# NRF52.net
KiCad netlist of a schematic drawn in Altium Designer
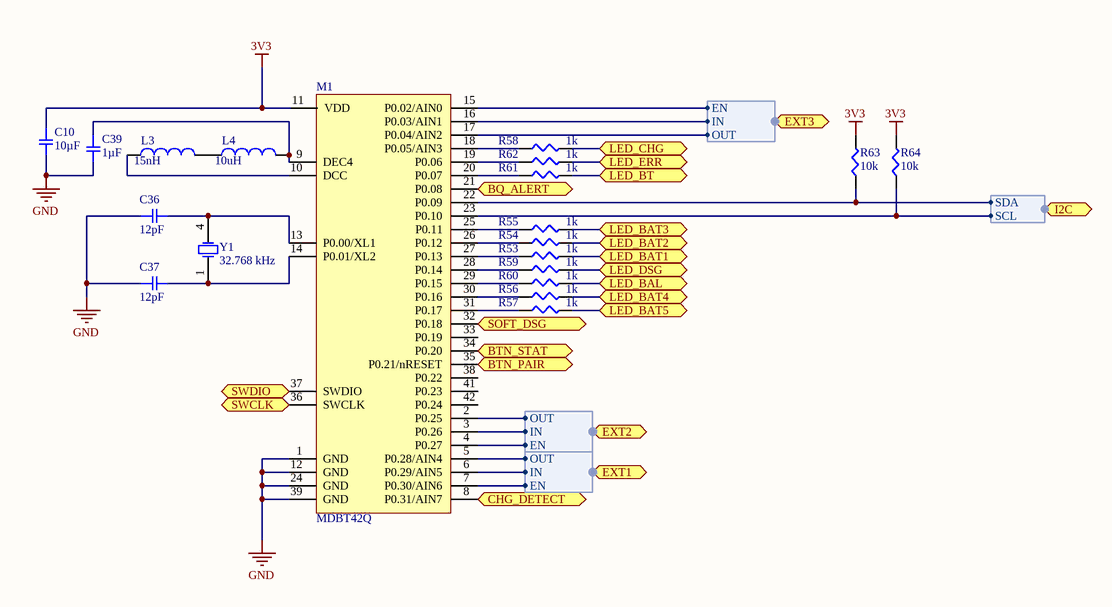
[diagram p0: NRF52.SchDoc]

(export (version "E")
  (design (tool "Eeschema 10.0.6"))
  (components
    (comp (ref "C10")
      (value "10µF")
      (footprint "SMD-0603C")
      (description "CAP CER 10UF 6.3V X5R 0603")
      (fields
        (field (name "DIGI-KEY PART NUMBER") "490-10467-1-ND")
        (field (name "PART NUMBER") "GRM185R60J106ME15D")
      )
      (libsource (lib "capacitor_murata_0603") (part "GRM185R60J106ME15D"))
    )
    (comp (ref "C36")
      (value "12pF")
      (footprint "SMD-0603C")
      (description "CAP CER 12PF 50V NP0 0603")
      (fields
        (field (name "DIGI-KEY PART NUMBER") "490-6045-1-ND")
        (field (name "PART NUMBER") "GCM1885C1H120JA16D")
      )
      (libsource (lib "capacitor_murata_0603") (part "GCM1885C1H120JA16D"))
    )
    (comp (ref "C37")
      (value "12pF")
      (footprint "SMD-0603C")
      (description "CAP CER 12PF 50V NP0 0603")
      (fields
        (field (name "DIGI-KEY PART NUMBER") "490-6045-1-ND")
        (field (name "PART NUMBER") "GCM1885C1H120JA16D")
      )
      (libsource (lib "capacitor_murata_0603") (part "GCM1885C1H120JA16D"))
    )
    (comp (ref "C39")
      (value "1µF")
      (footprint "SMD-0603C")
      (description "CAP CER 1UF 16V X7R 0603")
      (fields
        (field (name "DIGI-KEY PART NUMBER") "490-5241-1-ND")
        (field (name "PART NUMBER") "GCM188R71C105KA64D")
      )
      (libsource (lib "capacitor_murata_0603") (part "GCM188R71C105KA64D"))
    )
    (comp (ref "L3")
      (value "15nH")
      (footprint "0402-A")
      (description "Inductor")
      (fields (field (name "PUBLISHER") "Altium Limited"))
      (libsource (lib "Miscellaneous Devices") (part "Inductor"))
    )
    (comp (ref "L4")
      (value "10uH")
      (footprint "0402-A")
      (description "Inductor")
      (fields (field (name "PUBLISHER") "Altium Limited"))
      (libsource (lib "Miscellaneous Devices") (part "Inductor"))
    )
    (comp (ref "M1")
      (value "MDBT42Q")
      (footprint "MDBT42Q")
      (description "nRF52832 module")
      (libsource (lib "Components") (part "MDBT42Q"))
    )
    (comp (ref "R53")
      (value "1k")
      (footprint "SMD-0603-RES")
      (description "RES SMD 1K OHM 1% 1/10W 0603")
      (fields
        (field (name "PART NUMBER") "ERJ-3EKF1001V")
        (field (name "DIGI-KEY PART NUMBER") "P1.00KHCT-ND")
      )
      (libsource (lib "Panasonic_ERJ_0603") (part "ERJ-3EKF1001V"))
    )
    (comp (ref "R54")
      (value "1k")
      (footprint "SMD-0603-RES")
      (description "RES SMD 1K OHM 1% 1/10W 0603")
      (fields
        (field (name "PART NUMBER") "ERJ-3EKF1001V")
        (field (name "DIGI-KEY PART NUMBER") "P1.00KHCT-ND")
      )
      (libsource (lib "Panasonic_ERJ_0603") (part "ERJ-3EKF1001V"))
    )
    (comp (ref "R55")
      (value "1k")
      (footprint "SMD-0603-RES")
      (description "RES SMD 1K OHM 1% 1/10W 0603")
      (fields
        (field (name "PART NUMBER") "ERJ-3EKF1001V")
        (field (name "DIGI-KEY PART NUMBER") "P1.00KHCT-ND")
      )
      (libsource (lib "Panasonic_ERJ_0603") (part "ERJ-3EKF1001V"))
    )
    (comp (ref "R56")
      (value "1k")
      (footprint "SMD-0603-RES")
      (description "RES SMD 1K OHM 1% 1/10W 0603")
      (fields
        (field (name "PART NUMBER") "ERJ-3EKF1001V")
        (field (name "DIGI-KEY PART NUMBER") "P1.00KHCT-ND")
      )
      (libsource (lib "Panasonic_ERJ_0603") (part "ERJ-3EKF1001V"))
    )
    (comp (ref "R57")
      (value "1k")
      (footprint "SMD-0603-RES")
      (description "RES SMD 1K OHM 1% 1/10W 0603")
      (fields
        (field (name "PART NUMBER") "ERJ-3EKF1001V")
        (field (name "DIGI-KEY PART NUMBER") "P1.00KHCT-ND")
      )
      (libsource (lib "Panasonic_ERJ_0603") (part "ERJ-3EKF1001V"))
    )
    (comp (ref "R58")
      (value "1k")
      (footprint "SMD-0603-RES")
      (description "RES SMD 1K OHM 1% 1/10W 0603")
      (fields
        (field (name "PART NUMBER") "ERJ-3EKF1001V")
        (field (name "DIGI-KEY PART NUMBER") "P1.00KHCT-ND")
      )
      (libsource (lib "Panasonic_ERJ_0603") (part "ERJ-3EKF1001V"))
    )
    (comp (ref "R59")
      (value "1k")
      (footprint "SMD-0603-RES")
      (description "RES SMD 1K OHM 1% 1/10W 0603")
      (fields
        (field (name "PART NUMBER") "ERJ-3EKF1001V")
        (field (name "DIGI-KEY PART NUMBER") "P1.00KHCT-ND")
      )
      (libsource (lib "Panasonic_ERJ_0603") (part "ERJ-3EKF1001V"))
    )
    (comp (ref "R60")
      (value "1k")
      (footprint "SMD-0603-RES")
      (description "RES SMD 1K OHM 1% 1/10W 0603")
      (fields
        (field (name "PART NUMBER") "ERJ-3EKF1001V")
        (field (name "DIGI-KEY PART NUMBER") "P1.00KHCT-ND")
      )
      (libsource (lib "Panasonic_ERJ_0603") (part "ERJ-3EKF1001V"))
    )
    (comp (ref "R61")
      (value "1k")
      (footprint "SMD-0603-RES")
      (description "RES SMD 1K OHM 1% 1/10W 0603")
      (fields
        (field (name "PART NUMBER") "ERJ-3EKF1001V")
        (field (name "DIGI-KEY PART NUMBER") "P1.00KHCT-ND")
      )
      (libsource (lib "Panasonic_ERJ_0603") (part "ERJ-3EKF1001V"))
    )
    (comp (ref "R62")
      (value "1k")
      (footprint "SMD-0603-RES")
      (description "RES SMD 1K OHM 1% 1/10W 0603")
      (fields
        (field (name "PART NUMBER") "ERJ-3EKF1001V")
        (field (name "DIGI-KEY PART NUMBER") "P1.00KHCT-ND")
      )
      (libsource (lib "Panasonic_ERJ_0603") (part "ERJ-3EKF1001V"))
    )
    (comp (ref "R63")
      (value "10k")
      (footprint "SMD-0603-RES")
      (description "RES SMD 10K OHM 1% 1/10W 0603")
      (fields
        (field (name "PART NUMBER") "ERJ-3EKF1002V")
        (field (name "DIGI-KEY PART NUMBER") "P10.0KHCT-ND")
      )
      (libsource (lib "Panasonic_ERJ_0603") (part "ERJ-3EKF1002V"))
    )
    (comp (ref "R64")
      (value "10k")
      (footprint "SMD-0603-RES")
      (description "RES SMD 10K OHM 1% 1/10W 0603")
      (fields
        (field (name "PART NUMBER") "ERJ-3EKF1002V")
        (field (name "DIGI-KEY PART NUMBER") "P10.0KHCT-ND")
      )
      (libsource (lib "Panasonic_ERJ_0603") (part "ERJ-3EKF1002V"))
    )
    (comp (ref "Y1")
      (value "32.768 kHz")
      (footprint "LFXTAL")
      (description "LFXTAL016178")
      (fields (field (name "PUBLISHER") "Altium Limited"))
      (libsource (lib "Components") (part "LFXTAL016178"))
    )
  )
  (nets
    (net (code "3") (name "/BQ_ALERT") (class "Default")
      (node (ref "M1") (pin "21") (pinfunction "P0.08_21") (pintype "passive"))
    )
    (net (code "4") (name "/BTN_PAIR") (class "Default")
      (node (ref "M1") (pin "35") (pinfunction "P0.21/nRESET_35") (pintype "passive"))
    )
    (net (code "5") (name "/BTN_STAT") (class "Default")
      (node (ref "M1") (pin "34") (pinfunction "P0.20_34") (pintype "passive"))
    )
    (net (code "6") (name "/CHG_DETECT") (class "Default")
      (node (ref "M1") (pin "8") (pinfunction "P0.31/AIN7_8") (pintype "passive"))
    )
    (net (code "7") (name "/LED_BAL") (class "Default")
      (node (ref "R60") (pin "2") (pinfunction "2_2") (pintype "passive"))
    )
    (net (code "8") (name "/LED_BAT1") (class "Default")
      (node (ref "R53") (pin "2") (pinfunction "2_2") (pintype "passive"))
    )
    (net (code "9") (name "/LED_BAT2") (class "Default")
      (node (ref "R54") (pin "2") (pinfunction "2_2") (pintype "passive"))
    )
    (net (code "10") (name "/LED_BAT3") (class "Default")
      (node (ref "R55") (pin "2") (pinfunction "2_2") (pintype "passive"))
    )
    (net (code "11") (name "/LED_BAT4") (class "Default")
      (node (ref "R56") (pin "2") (pinfunction "2_2") (pintype "passive"))
    )
    (net (code "12") (name "/LED_BAT5") (class "Default")
      (node (ref "R57") (pin "2") (pinfunction "2_2") (pintype "passive"))
    )
    (net (code "13") (name "/LED_BT") (class "Default")
      (node (ref "R61") (pin "2") (pinfunction "2_2") (pintype "passive"))
    )
    (net (code "14") (name "/LED_CHG") (class "Default")
      (node (ref "R58") (pin "2") (pinfunction "2_2") (pintype "passive"))
    )
    (net (code "15") (name "/LED_DSG") (class "Default")
      (node (ref "R59") (pin "2") (pinfunction "2_2") (pintype "passive"))
    )
    (net (code "16") (name "/LED_ERR") (class "Default")
      (node (ref "R62") (pin "2") (pinfunction "2_2") (pintype "passive"))
    )
    (net (code "17") (name "/SCL") (class "Default")
      (node (ref "M1") (pin "23") (pinfunction "P0.10_23") (pintype "passive"))
      (node (ref "R64") (pin "1") (pinfunction "1_1") (pintype "passive"))
    )
    (net (code "18") (name "/SDA") (class "Default")
      (node (ref "M1") (pin "22") (pinfunction "P0.09_22") (pintype "passive"))
      (node (ref "R63") (pin "1") (pinfunction "1_1") (pintype "passive"))
    )
    (net (code "19") (name "/SOFT_DSG") (class "Default")
      (node (ref "M1") (pin "32") (pinfunction "P0.18_32") (pintype "passive"))
    )
    (net (code "20") (name "/SWCLK") (class "Default")
      (node (ref "M1") (pin "36") (pinfunction "SWCLK_36") (pintype "passive"))
    )
    (net (code "21") (name "/SWDIO") (class "Default")
      (node (ref "M1") (pin "37") (pinfunction "SWDIO_37") (pintype "passive"))
    )
    (net (code "24") (name "3V3") (class "Default")
      (node (ref "C10") (pin "1") (pinfunction "1_1") (pintype "passive"))
      (node (ref "M1") (pin "11") (pinfunction "VDD_11") (pintype "passive"))
      (node (ref "R63") (pin "2") (pinfunction "2_2") (pintype "passive"))
      (node (ref "R64") (pin "2") (pinfunction "2_2") (pintype "passive"))
    )
    (net (code "25") (name "GND") (class "Default")
      (node (ref "C10") (pin "2") (pinfunction "2_2") (pintype "passive"))
      (node (ref "C36") (pin "1") (pinfunction "1_1") (pintype "passive"))
      (node (ref "C37") (pin "1") (pinfunction "1_1") (pintype "passive"))
      (node (ref "C39") (pin "2") (pinfunction "2_2") (pintype "passive"))
      (node (ref "M1") (pin "1") (pinfunction "GND_1") (pintype "passive"))
      (node (ref "M1") (pin "12") (pinfunction "GND_12") (pintype "passive"))
      (node (ref "M1") (pin "24") (pinfunction "GND_24") (pintype "passive"))
      (node (ref "M1") (pin "39") (pinfunction "GND_39") (pintype "passive"))
    )
    (net (code "26") (name "Net-(L3-Pad2)") (class "Default")
      (node (ref "L3") (pin "2") (pinfunction "2_2") (pintype "passive"))
      (node (ref "L4") (pin "1") (pinfunction "1_1") (pintype "passive"))
    )
    (net (code "27") (name "Net-(M1-DCC)") (class "Default")
      (node (ref "L3") (pin "1") (pinfunction "1_1") (pintype "passive"))
      (node (ref "M1") (pin "10") (pinfunction "DCC_10") (pintype "passive"))
    )
    (net (code "28") (name "Net-(M1-DEC4)") (class "Default")
      (node (ref "C39") (pin "1") (pinfunction "1_1") (pintype "passive"))
      (node (ref "L4") (pin "2") (pinfunction "2_2") (pintype "passive"))
      (node (ref "M1") (pin "9") (pinfunction "DEC4_9") (pintype "passive"))
    )
    (net (code "29") (name "Net-(M1-P0.00{slash}XL1)") (class "Default")
      (node (ref "C36") (pin "2") (pinfunction "2_2") (pintype "passive"))
      (node (ref "M1") (pin "13") (pinfunction "P0.00/XL1_13") (pintype "passive"))
      (node (ref "Y1") (pin "4") (pinfunction "OSC2_4") (pintype "passive"))
    )
    (net (code "30") (name "Net-(M1-P0.01{slash}XL2)") (class "Default")
      (node (ref "C37") (pin "2") (pinfunction "2_2") (pintype "passive"))
      (node (ref "M1") (pin "14") (pinfunction "P0.01/XL2_14") (pintype "passive"))
      (node (ref "Y1") (pin "1") (pinfunction "OSC1_1") (pintype "passive"))
    )
    (net (code "31") (name "Net-(M1-P0.05{slash}AIN3)") (class "Default")
      (node (ref "M1") (pin "18") (pinfunction "P0.05/AIN3_18") (pintype "passive"))
      (node (ref "R58") (pin "1") (pinfunction "1_1") (pintype "passive"))
    )
    (net (code "32") (name "Net-(M1-P0.06)") (class "Default")
      (node (ref "M1") (pin "19") (pinfunction "P0.06_19") (pintype "passive"))
      (node (ref "R62") (pin "1") (pinfunction "1_1") (pintype "passive"))
    )
    (net (code "33") (name "Net-(M1-P0.07)") (class "Default")
      (node (ref "M1") (pin "20") (pinfunction "P0.07_20") (pintype "passive"))
      (node (ref "R61") (pin "1") (pinfunction "1_1") (pintype "passive"))
    )
    (net (code "34") (name "Net-(M1-P0.11)") (class "Default")
      (node (ref "M1") (pin "25") (pinfunction "P0.11_25") (pintype "passive"))
      (node (ref "R55") (pin "1") (pinfunction "1_1") (pintype "passive"))
    )
    (net (code "35") (name "Net-(M1-P0.12)") (class "Default")
      (node (ref "M1") (pin "26") (pinfunction "P0.12_26") (pintype "passive"))
      (node (ref "R54") (pin "1") (pinfunction "1_1") (pintype "passive"))
    )
    (net (code "36") (name "Net-(M1-P0.13)") (class "Default")
      (node (ref "M1") (pin "27") (pinfunction "P0.13_27") (pintype "passive"))
      (node (ref "R53") (pin "1") (pinfunction "1_1") (pintype "passive"))
    )
    (net (code "37") (name "Net-(M1-P0.14)") (class "Default")
      (node (ref "M1") (pin "28") (pinfunction "P0.14_28") (pintype "passive"))
      (node (ref "R59") (pin "1") (pinfunction "1_1") (pintype "passive"))
    )
    (net (code "38") (name "Net-(M1-P0.15)") (class "Default")
      (node (ref "M1") (pin "29") (pinfunction "P0.15_29") (pintype "passive"))
      (node (ref "R60") (pin "1") (pinfunction "1_1") (pintype "passive"))
    )
    (net (code "39") (name "Net-(M1-P0.16)") (class "Default")
      (node (ref "M1") (pin "30") (pinfunction "P0.16_30") (pintype "passive"))
      (node (ref "R56") (pin "1") (pinfunction "1_1") (pintype "passive"))
    )
    (net (code "40") (name "Net-(M1-P0.17)") (class "Default")
      (node (ref "M1") (pin "31") (pinfunction "P0.17_31") (pintype "passive"))
      (node (ref "R57") (pin "1") (pinfunction "1_1") (pintype "passive"))
    )
    (net (code "41") (name "unconnected-(M1-P0.02{slash}AIN0-Pad15)") (class "Default")
      (node (ref "M1") (pin "15") (pinfunction "P0.02/AIN0_15") (pintype "passive"))
    )
    (net (code "42") (name "unconnected-(M1-P0.03{slash}AIN1-Pad16)") (class "Default")
      (node (ref "M1") (pin "16") (pinfunction "P0.03/AIN1_16") (pintype "passive"))
    )
    (net (code "43") (name "unconnected-(M1-P0.04{slash}AIN2-Pad17)") (class "Default")
      (node (ref "M1") (pin "17") (pinfunction "P0.04/AIN2_17") (pintype "passive"))
    )
    (net (code "44") (name "unconnected-(M1-P0.19-Pad33)") (class "Default")
      (node (ref "M1") (pin "33") (pinfunction "P0.19_33") (pintype "passive"))
    )
    (net (code "45") (name "unconnected-(M1-P0.22-Pad38)") (class "Default")
      (node (ref "M1") (pin "38") (pinfunction "P0.22_38") (pintype "passive"))
    )
    (net (code "46") (name "unconnected-(M1-P0.23-Pad41)") (class "Default")
      (node (ref "M1") (pin "41") (pinfunction "P0.23_41") (pintype "passive"))
    )
    (net (code "47") (name "unconnected-(M1-P0.24-Pad42)") (class "Default")
      (node (ref "M1") (pin "42") (pinfunction "P0.24_42") (pintype "passive"))
    )
    (net (code "48") (name "unconnected-(M1-P0.25-Pad2)") (class "Default")
      (node (ref "M1") (pin "2") (pinfunction "P0.25_2") (pintype "passive"))
    )
    (net (code "49") (name "unconnected-(M1-P0.26-Pad3)") (class "Default")
      (node (ref "M1") (pin "3") (pinfunction "P0.26_3") (pintype "passive"))
    )
    (net (code "50") (name "unconnected-(M1-P0.27-Pad4)") (class "Default")
      (node (ref "M1") (pin "4") (pinfunction "P0.27_4") (pintype "passive"))
    )
    (net (code "51") (name "unconnected-(M1-P0.28{slash}AIN4-Pad5)") (class "Default")
      (node (ref "M1") (pin "5") (pinfunction "P0.28/AIN4_5") (pintype "passive"))
    )
    (net (code "52") (name "unconnected-(M1-P0.29{slash}AIN5-Pad6)") (class "Default")
      (node (ref "M1") (pin "6") (pinfunction "P0.29/AIN5_6") (pintype "passive"))
    )
    (net (code "53") (name "unconnected-(M1-P0.30{slash}AIN6-Pad7)") (class "Default")
      (node (ref "M1") (pin "7") (pinfunction "P0.30/AIN6_7") (pintype "passive"))
    )
  )
)
